# pvinvertershield32_v2.net
KiCad netlist of a schematic drawn in EAGLE
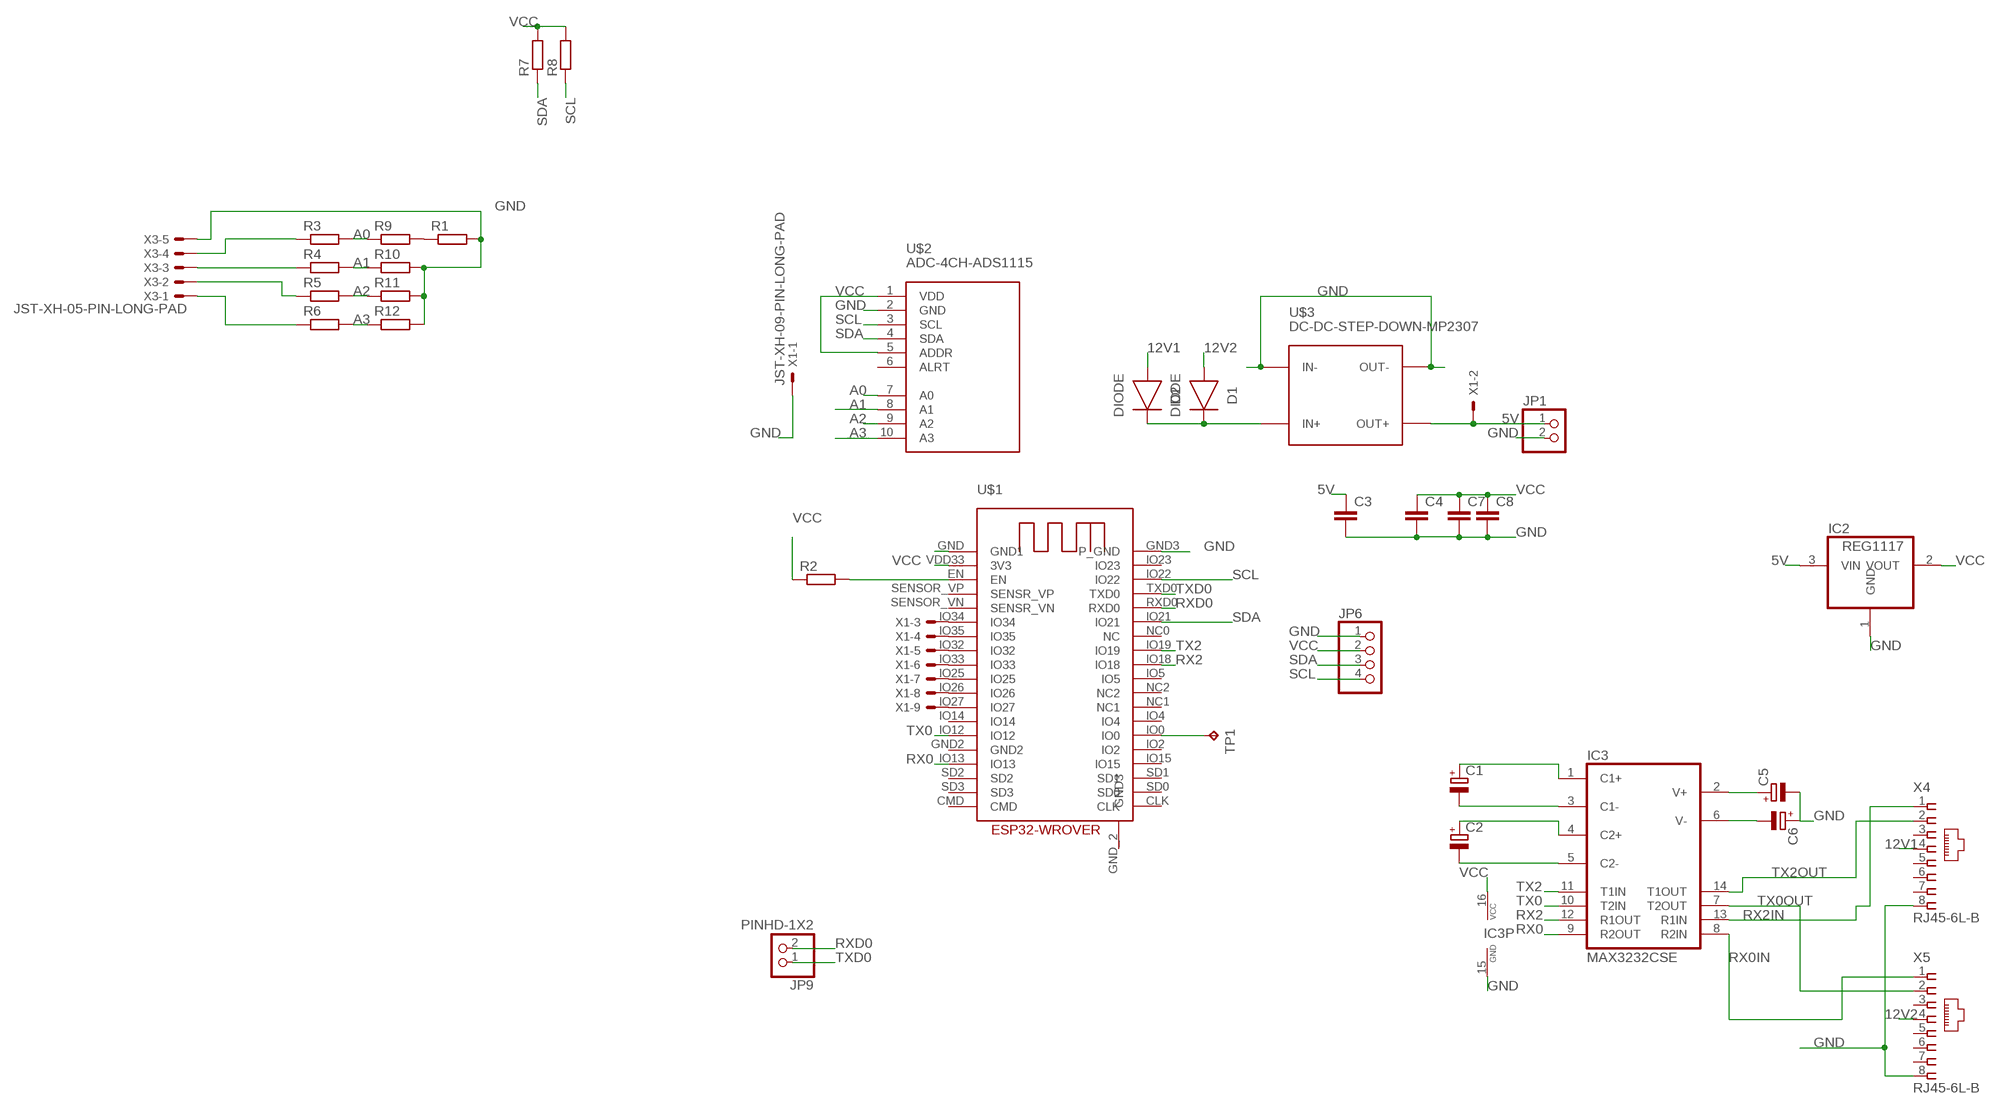
[diagram p0: schematic, sheet 1]

(export (version "E")
  (design (tool "Eeschema 10.0.6"))
  (components
    (comp (ref "C1")
      (value "CPOL-EUE2.5-6")
      (footprint "eagle-import:E2,5-6")
      (libsource (lib "eagle-import") (part "CPOL-EUE2.5-6"))
    )
    (comp (ref "C2")
      (value "CPOL-EUE2.5-6")
      (footprint "eagle-import:E2,5-6")
      (libsource (lib "eagle-import") (part "CPOL-EUE2.5-6"))
    )
    (comp (ref "C3")
      (value "C-EUC1210")
      (footprint "eagle-import:C1210")
      (libsource (lib "eagle-import") (part "C-EUC1210"))
    )
    (comp (ref "C4")
      (value "C-EUC1210")
      (footprint "eagle-import:C1210")
      (libsource (lib "eagle-import") (part "C-EUC1210"))
    )
    (comp (ref "C5")
      (value "CPOL-EUE2.5-6")
      (footprint "eagle-import:E2,5-6")
      (libsource (lib "eagle-import") (part "CPOL-EUE2.5-6"))
    )
    (comp (ref "C6")
      (value "CPOL-EUE2.5-6")
      (footprint "eagle-import:E2,5-6")
      (libsource (lib "eagle-import") (part "CPOL-EUE2.5-6"))
    )
    (comp (ref "C7")
      (value "C-EUC1210")
      (footprint "eagle-import:C1210")
      (libsource (lib "eagle-import") (part "C-EUC1210"))
    )
    (comp (ref "C8")
      (value "C-EUC1210")
      (footprint "eagle-import:C1210")
      (libsource (lib "eagle-import") (part "C-EUC1210"))
    )
    (comp (ref "D1")
      (value "DIODE")
      (footprint "eagle-import:DIOMELF5024")
      (libsource (lib "eagle-import") (part "DIODEDO-213AB(5025-METRIC)_"))
    )
    (comp (ref "D2")
      (value "DIODE")
      (footprint "eagle-import:DIOMELF5024")
      (libsource (lib "eagle-import") (part "DIODEDO-213AB(5025-METRIC)_"))
    )
    (comp (ref "IC2")
      (value "REG1117")
      (footprint "eagle-import:SOT223")
      (libsource (lib "eagle-import") (part "REG1117"))
    )
    (comp (ref "IC3")
      (value "MAX3232CSE")
      (footprint "eagle-import:SO16")
      (libsource (lib "eagle-import") (part "MAX3232SEC"))
    )
    (comp (ref "JP1")
      (value "PINHD-1X2")
      (footprint "eagle-import:1X02")
      (libsource (lib "eagle-import") (part "pinhead_325_PINHD-1X2"))
    )
    (comp (ref "JP6")
      (value "PINHD-1X4")
      (footprint "eagle-import:1X04")
      (libsource (lib "eagle-import") (part "PINHD-1X4"))
    )
    (comp (ref "JP9")
      (value "PINHD-1X2")
      (footprint "eagle-import:1X02")
      (libsource (lib "eagle-import") (part "PINHD-1X2"))
    )
    (comp (ref "R1")
      (value "R-EU_R0805")
      (footprint "eagle-import:R0805")
      (libsource (lib "eagle-import") (part "resistor_348_R-EU_R0805"))
    )
    (comp (ref "R2")
      (value "R-EU_R0805")
      (footprint "eagle-import:R0805")
      (libsource (lib "eagle-import") (part "R-EU_R0805"))
    )
    (comp (ref "R3")
      (value "R-EU_R0805")
      (footprint "eagle-import:R0805")
      (libsource (lib "eagle-import") (part "resistor_348_R-EU_R0805"))
    )
    (comp (ref "R4")
      (value "R-EU_R0805")
      (footprint "eagle-import:R0805")
      (libsource (lib "eagle-import") (part "resistor_348_R-EU_R0805"))
    )
    (comp (ref "R5")
      (value "R-EU_R0805")
      (footprint "eagle-import:R0805")
      (libsource (lib "eagle-import") (part "resistor_348_R-EU_R0805"))
    )
    (comp (ref "R6")
      (value "R-EU_R0805")
      (footprint "eagle-import:R0805")
      (libsource (lib "eagle-import") (part "resistor_348_R-EU_R0805"))
    )
    (comp (ref "R7")
      (value "R-EU_0207/10")
      (footprint "eagle-import:0207_10")
      (libsource (lib "eagle-import") (part "resistor_348_R-EU_0207/10"))
    )
    (comp (ref "R8")
      (value "R-EU_0207/10")
      (footprint "eagle-import:0207_10")
      (libsource (lib "eagle-import") (part "resistor_348_R-EU_0207/10"))
    )
    (comp (ref "R9")
      (value "R-EU_R0805")
      (footprint "eagle-import:R0805")
      (libsource (lib "eagle-import") (part "resistor_348_R-EU_R0805"))
    )
    (comp (ref "R10")
      (value "R-EU_R0805")
      (footprint "eagle-import:R0805")
      (libsource (lib "eagle-import") (part "resistor_348_R-EU_R0805"))
    )
    (comp (ref "R11")
      (value "R-EU_R0805")
      (footprint "eagle-import:R0805")
      (libsource (lib "eagle-import") (part "resistor_348_R-EU_R0805"))
    )
    (comp (ref "R12")
      (value "R-EU_R0805")
      (footprint "eagle-import:R0805")
      (libsource (lib "eagle-import") (part "resistor_348_R-EU_R0805"))
    )
    (comp (ref "TP1")
      (value "TPB2,54")
      (footprint "eagle-import:B2,54")
      (libsource (lib "eagle-import") (part "TPB2,54"))
    )
    (comp (ref "U$1")
      (value "ESP32-WROVER")
      (footprint "eagle-import:ESP32-WROVER")
      (libsource (lib "eagle-import") (part "ESP32-WROVER"))
    )
    (comp (ref "U$2")
      (value "ADC-4CH-ADS1115")
      (footprint "eagle-import:ADC-4CH-ADS1115")
      (libsource (lib "eagle-import") (part "ADC-4CH-ADS1115"))
    )
    (comp (ref "U$3")
      (value "DC-DC-STEP-DOWN-MP2307")
      (footprint "eagle-import:DC-DC-STEP-DOWN-MP2307")
      (libsource (lib "eagle-import") (part "DC-DC-STEP-DOWN-MP2307"))
    )
    (comp (ref "X1")
      (value "JST-XH-09-PIN-LONG-PAD")
      (footprint "eagle-import:JST-XH-09-PACKAGE-LONG-PAD")
      (libsource (lib "eagle-import") (part "JST-XH-09-PIN-LONG-PAD"))
    )
    (comp (ref "X3")
      (value "JST-XH-05-PIN-LONG-PAD")
      (footprint "eagle-import:JST-XH-05-PACKAGE-LONG-PAD")
      (libsource (lib "eagle-import") (part "JST-XH-05-PIN-LONG-PAD"))
    )
    (comp (ref "X4")
      (value "RJ45-6L-B")
      (footprint "eagle-import:RJ45-NO-SHIELD")
      (libsource (lib "eagle-import") (part "RJ45-6L-B"))
    )
    (comp (ref "X5")
      (value "RJ45-6L-B")
      (footprint "eagle-import:RJ45-NO-SHIELD")
      (libsource (lib "eagle-import") (part "RJ45-6L-B"))
    )
  )
  (nets
    (net (code "1") (name "/5V") (class "Default")
      (node (ref "C3") (pin "1") (pinfunction "1_1") (pintype "passive"))
      (node (ref "IC2") (pin "3") (pinfunction "VIN_3") (pintype "input"))
      (node (ref "JP1") (pin "1") (pinfunction "1_1") (pintype "passive"))
      (node (ref "U$3") (pin "OUT+") (pinfunction "OUT+_OUT+") (pintype "bidirectional"))
      (node (ref "X1") (pin "2") (pinfunction "S_2") (pintype "passive"))
    )
    (net (code "2") (name "/12V1") (class "Default")
      (node (ref "D2") (pin "2") (pinfunction "A_2") (pintype "passive"))
      (node (ref "X4") (pin "4") (pinfunction "4_4") (pintype "passive"))
    )
    (net (code "3") (name "/12V2") (class "Default")
      (node (ref "D1") (pin "2") (pinfunction "A_2") (pintype "passive"))
      (node (ref "X5") (pin "4") (pinfunction "4_4") (pintype "passive"))
    )
    (net (code "4") (name "/A0") (class "Default")
      (node (ref "R3") (pin "2") (pinfunction "2_2") (pintype "passive"))
      (node (ref "R9") (pin "1") (pinfunction "1_1") (pintype "passive"))
      (node (ref "U$2") (pin "7") (pinfunction "A0_7") (pintype "input"))
    )
    (net (code "5") (name "/A1") (class "Default")
      (node (ref "R10") (pin "1") (pinfunction "1_1") (pintype "passive"))
      (node (ref "R4") (pin "2") (pinfunction "2_2") (pintype "passive"))
      (node (ref "U$2") (pin "8") (pinfunction "A1_8") (pintype "input"))
    )
    (net (code "6") (name "/A2") (class "Default")
      (node (ref "R11") (pin "1") (pinfunction "1_1") (pintype "passive"))
      (node (ref "R5") (pin "2") (pinfunction "2_2") (pintype "passive"))
      (node (ref "U$2") (pin "9") (pinfunction "A2_9") (pintype "input"))
    )
    (net (code "7") (name "/A3") (class "Default")
      (node (ref "R12") (pin "1") (pinfunction "1_1") (pintype "passive"))
      (node (ref "R6") (pin "2") (pinfunction "2_2") (pintype "passive"))
      (node (ref "U$2") (pin "10") (pinfunction "A3_10") (pintype "input"))
    )
    (net (code "8") (name "/GND") (class "Default")
      (node (ref "C3") (pin "2") (pinfunction "2_2") (pintype "passive"))
      (node (ref "C4") (pin "2") (pinfunction "2_2") (pintype "passive"))
      (node (ref "C5") (pin "-") (pinfunction "-_-") (pintype "passive"))
      (node (ref "C6") (pin "+") (pinfunction "+_+") (pintype "passive"))
      (node (ref "C7") (pin "2") (pinfunction "2_2") (pintype "passive"))
      (node (ref "C8") (pin "2") (pinfunction "2_2") (pintype "passive"))
      (node (ref "IC2") (pin "1") (pinfunction "GND_1") (pintype "power_in"))
      (node (ref "IC3") (pin "15") (pinfunction "GND_15") (pintype "power_in"))
      (node (ref "JP1") (pin "2") (pinfunction "2_2") (pintype "passive"))
      (node (ref "JP6") (pin "1") (pinfunction "1_1") (pintype "passive"))
      (node (ref "R1") (pin "2") (pinfunction "2_2") (pintype "passive"))
      (node (ref "R10") (pin "2") (pinfunction "2_2") (pintype "passive"))
      (node (ref "R11") (pin "2") (pinfunction "2_2") (pintype "passive"))
      (node (ref "R12") (pin "2") (pinfunction "2_2") (pintype "passive"))
      (node (ref "U$1") (pin "GND") (pinfunction "GND1_GND") (pintype "bidirectional"))
      (node (ref "U$1") (pin "GND3") (pinfunction "P_GND_GND3") (pintype "bidirectional"))
      (node (ref "U$2") (pin "2") (pinfunction "GND_2") (pintype "power_in"))
      (node (ref "U$3") (pin "IN-") (pinfunction "IN-_IN-") (pintype "bidirectional"))
      (node (ref "U$3") (pin "OUT-") (pinfunction "OUT-_OUT-") (pintype "bidirectional"))
      (node (ref "X1") (pin "1") (pinfunction "S_1") (pintype "passive"))
      (node (ref "X3") (pin "5") (pinfunction "S_5") (pintype "passive"))
      (node (ref "X4") (pin "8") (pinfunction "8_8") (pintype "passive"))
      (node (ref "X5") (pin "8") (pinfunction "8_8") (pintype "passive"))
    )
    (net (code "9") (name "/RX0") (class "Default")
      (node (ref "IC3") (pin "9") (pinfunction "R2OUT_9") (pintype "output"))
      (node (ref "U$1") (pin "IO13") (pinfunction "IO13_IO13") (pintype "bidirectional"))
    )
    (net (code "10") (name "/RX0IN") (class "Default")
      (node (ref "IC3") (pin "8") (pinfunction "R2IN_8") (pintype "input"))
      (node (ref "X5") (pin "1") (pinfunction "1_1") (pintype "passive"))
    )
    (net (code "11") (name "/RX2") (class "Default")
      (node (ref "IC3") (pin "12") (pinfunction "R1OUT_12") (pintype "output"))
      (node (ref "U$1") (pin "IO18") (pinfunction "IO18_IO18") (pintype "bidirectional"))
    )
    (net (code "12") (name "/RX2IN") (class "Default")
      (node (ref "IC3") (pin "13") (pinfunction "R1IN_13") (pintype "input"))
      (node (ref "X4") (pin "1") (pinfunction "1_1") (pintype "passive"))
    )
    (net (code "13") (name "/RXD0") (class "Default")
      (node (ref "JP9") (pin "2") (pinfunction "2_2") (pintype "passive"))
      (node (ref "U$1") (pin "RXD0") (pinfunction "RXD0_RXD0") (pintype "bidirectional"))
    )
    (net (code "14") (name "/SCL") (class "Default")
      (node (ref "JP6") (pin "4") (pinfunction "4_4") (pintype "passive"))
      (node (ref "R8") (pin "1") (pinfunction "1_1") (pintype "passive"))
      (node (ref "U$1") (pin "IO22") (pinfunction "IO22_IO22") (pintype "bidirectional"))
      (node (ref "U$2") (pin "3") (pinfunction "SCL_3") (pintype "bidirectional"))
    )
    (net (code "15") (name "/SDA") (class "Default")
      (node (ref "JP6") (pin "3") (pinfunction "3_3") (pintype "passive"))
      (node (ref "R7") (pin "1") (pinfunction "1_1") (pintype "passive"))
      (node (ref "U$1") (pin "IO21") (pinfunction "IO21_IO21") (pintype "bidirectional"))
      (node (ref "U$2") (pin "4") (pinfunction "SDA_4") (pintype "bidirectional"))
    )
    (net (code "16") (name "/TX0") (class "Default")
      (node (ref "IC3") (pin "10") (pinfunction "T2IN_10") (pintype "input"))
      (node (ref "U$1") (pin "IO12") (pinfunction "IO12_IO12") (pintype "bidirectional"))
    )
    (net (code "17") (name "/TX0OUT") (class "Default")
      (node (ref "IC3") (pin "7") (pinfunction "T2OUT_7") (pintype "output"))
      (node (ref "X5") (pin "2") (pinfunction "2_2") (pintype "passive"))
    )
    (net (code "18") (name "/TX2") (class "Default")
      (node (ref "IC3") (pin "11") (pinfunction "T1IN_11") (pintype "input"))
      (node (ref "U$1") (pin "IO19") (pinfunction "IO19_IO19") (pintype "bidirectional"))
    )
    (net (code "19") (name "/TX2OUT") (class "Default")
      (node (ref "IC3") (pin "14") (pinfunction "T1OUT_14") (pintype "output"))
      (node (ref "X4") (pin "2") (pinfunction "2_2") (pintype "passive"))
    )
    (net (code "20") (name "/TXD0") (class "Default")
      (node (ref "JP9") (pin "1") (pinfunction "1_1") (pintype "passive"))
      (node (ref "U$1") (pin "TXD0") (pinfunction "TXD0_TXD0") (pintype "bidirectional"))
    )
    (net (code "21") (name "/VCC") (class "Default")
      (node (ref "C4") (pin "1") (pinfunction "1_1") (pintype "passive"))
      (node (ref "C7") (pin "1") (pinfunction "1_1") (pintype "passive"))
      (node (ref "C8") (pin "1") (pinfunction "1_1") (pintype "passive"))
      (node (ref "IC2") (pin "2") (pinfunction "VOUT_2") (pintype "output"))
      (node (ref "IC3") (pin "16") (pinfunction "VCC_16") (pintype "power_in"))
      (node (ref "JP6") (pin "2") (pinfunction "2_2") (pintype "passive"))
      (node (ref "R2") (pin "1") (pinfunction "1_1") (pintype "passive"))
      (node (ref "R7") (pin "2") (pinfunction "2_2") (pintype "passive"))
      (node (ref "R8") (pin "2") (pinfunction "2_2") (pintype "passive"))
      (node (ref "U$1") (pin "VDD33") (pinfunction "3V3_VDD33") (pintype "bidirectional"))
      (node (ref "U$2") (pin "1") (pinfunction "VDD_1") (pintype "power_in"))
      (node (ref "U$2") (pin "5") (pinfunction "ADDR_5") (pintype "bidirectional"))
    )
    (net (code "22") (name "Net-(D1-C)") (class "Default")
      (node (ref "D1") (pin "1") (pinfunction "C_1") (pintype "passive"))
      (node (ref "D2") (pin "1") (pinfunction "C_1") (pintype "passive"))
      (node (ref "U$3") (pin "IN+") (pinfunction "IN+_IN+") (pintype "bidirectional"))
    )
    (net (code "23") (name "Net-(IC3A-C1+)") (class "Default")
      (node (ref "C1") (pin "+") (pinfunction "+_+") (pintype "passive"))
      (node (ref "IC3") (pin "1") (pinfunction "C1+_1") (pintype "bidirectional"))
    )
    (net (code "24") (name "Net-(IC3A-C1-)") (class "Default")
      (node (ref "C1") (pin "-") (pinfunction "-_-") (pintype "passive"))
      (node (ref "IC3") (pin "3") (pinfunction "C1-_3") (pintype "bidirectional"))
    )
    (net (code "25") (name "Net-(IC3A-C2+)") (class "Default")
      (node (ref "C2") (pin "+") (pinfunction "+_+") (pintype "passive"))
      (node (ref "IC3") (pin "4") (pinfunction "C2+_4") (pintype "bidirectional"))
    )
    (net (code "26") (name "Net-(IC3A-C2-)") (class "Default")
      (node (ref "C2") (pin "-") (pinfunction "-_-") (pintype "passive"))
      (node (ref "IC3") (pin "5") (pinfunction "C2-_5") (pintype "bidirectional"))
    )
    (net (code "27") (name "Net-(IC3A-V+)") (class "Default")
      (node (ref "C5") (pin "+") (pinfunction "+_+") (pintype "passive"))
      (node (ref "IC3") (pin "2") (pinfunction "V+_2") (pintype "bidirectional"))
    )
    (net (code "28") (name "Net-(IC3A-V-)") (class "Default")
      (node (ref "C6") (pin "-") (pinfunction "-_-") (pintype "passive"))
      (node (ref "IC3") (pin "6") (pinfunction "V-_6") (pintype "bidirectional"))
    )
    (net (code "29") (name "Net-(R1-Pad1)") (class "Default")
      (node (ref "R1") (pin "1") (pinfunction "1_1") (pintype "passive"))
      (node (ref "R9") (pin "2") (pinfunction "2_2") (pintype "passive"))
    )
    (net (code "30") (name "Net-(R2-Pad2)") (class "Default")
      (node (ref "R2") (pin "2") (pinfunction "2_2") (pintype "passive"))
      (node (ref "U$1") (pin "EN") (pinfunction "EN_EN") (pintype "bidirectional"))
    )
    (net (code "31") (name "Net-(TP1-PadTP)") (class "Default")
      (node (ref "TP1") (pin "TP") (pinfunction "TP_TP") (pintype "input"))
      (node (ref "U$1") (pin "IO0") (pinfunction "IO0_IO0") (pintype "bidirectional"))
    )
    (net (code "32") (name "Net-(X1C-S)") (class "Default")
      (node (ref "U$1") (pin "IO34") (pinfunction "IO34_IO34") (pintype "bidirectional"))
      (node (ref "X1") (pin "3") (pinfunction "S_3") (pintype "passive"))
    )
    (net (code "33") (name "Net-(X1D-S)") (class "Default")
      (node (ref "U$1") (pin "IO35") (pinfunction "IO35_IO35") (pintype "bidirectional"))
      (node (ref "X1") (pin "4") (pinfunction "S_4") (pintype "passive"))
    )
    (net (code "34") (name "Net-(X1E-S)") (class "Default")
      (node (ref "U$1") (pin "IO32") (pinfunction "IO32_IO32") (pintype "bidirectional"))
      (node (ref "X1") (pin "5") (pinfunction "S_5") (pintype "passive"))
    )
    (net (code "35") (name "Net-(X1F-S)") (class "Default")
      (node (ref "U$1") (pin "IO33") (pinfunction "IO33_IO33") (pintype "bidirectional"))
      (node (ref "X1") (pin "6") (pinfunction "S_6") (pintype "passive"))
    )
    (net (code "36") (name "Net-(X1G-S)") (class "Default")
      (node (ref "U$1") (pin "IO25") (pinfunction "IO25_IO25") (pintype "bidirectional"))
      (node (ref "X1") (pin "7") (pinfunction "S_7") (pintype "passive"))
    )
    (net (code "37") (name "Net-(X1H-S)") (class "Default")
      (node (ref "U$1") (pin "IO26") (pinfunction "IO26_IO26") (pintype "bidirectional"))
      (node (ref "X1") (pin "8") (pinfunction "S_8") (pintype "passive"))
    )
    (net (code "38") (name "Net-(X1I-S)") (class "Default")
      (node (ref "U$1") (pin "IO27") (pinfunction "IO27_IO27") (pintype "bidirectional"))
      (node (ref "X1") (pin "9") (pinfunction "S_9") (pintype "passive"))
    )
    (net (code "39") (name "Net-(X3A-S)") (class "Default")
      (node (ref "R6") (pin "1") (pinfunction "1_1") (pintype "passive"))
      (node (ref "X3") (pin "1") (pinfunction "S_1") (pintype "passive"))
    )
    (net (code "40") (name "Net-(X3B-S)") (class "Default")
      (node (ref "R5") (pin "1") (pinfunction "1_1") (pintype "passive"))
      (node (ref "X3") (pin "2") (pinfunction "S_2") (pintype "passive"))
    )
    (net (code "41") (name "Net-(X3C-S)") (class "Default")
      (node (ref "R4") (pin "1") (pinfunction "1_1") (pintype "passive"))
      (node (ref "X3") (pin "3") (pinfunction "S_3") (pintype "passive"))
    )
    (net (code "42") (name "Net-(X3D-S)") (class "Default")
      (node (ref "R3") (pin "1") (pinfunction "1_1") (pintype "passive"))
      (node (ref "X3") (pin "4") (pinfunction "S_4") (pintype "passive"))
    )
    (net (code "43") (name "unconnected-(U$1-GND3-PadGND_2)") (class "Default")
      (node (ref "U$1") (pin "GND_2") (pinfunction "GND3_GND_2") (pintype "bidirectional"))
    )
    (net (code "44") (name "unconnected-(U$1-NC-PadNC0)") (class "Default")
      (node (ref "U$1") (pin "NC0") (pinfunction "NC_NC0") (pintype "bidirectional"))
    )
    (net (code "45") (name "unconnected-(U$1-PadCLK)") (class "Default")
      (node (ref "U$1") (pin "CLK") (pinfunction "CLK_CLK") (pintype "bidirectional"))
    )
    (net (code "46") (name "unconnected-(U$1-PadCMD)") (class "Default")
      (node (ref "U$1") (pin "CMD") (pinfunction "CMD_CMD") (pintype "bidirectional"))
    )
    (net (code "47") (name "unconnected-(U$1-PadGND2)") (class "Default")
      (node (ref "U$1") (pin "GND2") (pinfunction "GND2_GND2") (pintype "bidirectional"))
    )
    (net (code "48") (name "unconnected-(U$1-PadIO2)") (class "Default")
      (node (ref "U$1") (pin "IO2") (pinfunction "IO2_IO2") (pintype "bidirectional"))
    )
    (net (code "49") (name "unconnected-(U$1-PadIO4)") (class "Default")
      (node (ref "U$1") (pin "IO4") (pinfunction "IO4_IO4") (pintype "bidirectional"))
    )
    (net (code "50") (name "unconnected-(U$1-PadIO5)") (class "Default")
      (node (ref "U$1") (pin "IO5") (pinfunction "IO5_IO5") (pintype "bidirectional"))
    )
    (net (code "51") (name "unconnected-(U$1-PadIO14)") (class "Default")
      (node (ref "U$1") (pin "IO14") (pinfunction "IO14_IO14") (pintype "bidirectional"))
    )
    (net (code "52") (name "unconnected-(U$1-PadIO15)") (class "Default")
      (node (ref "U$1") (pin "IO15") (pinfunction "IO15_IO15") (pintype "bidirectional"))
    )
    (net (code "53") (name "unconnected-(U$1-PadIO23)") (class "Default")
      (node (ref "U$1") (pin "IO23") (pinfunction "IO23_IO23") (pintype "bidirectional"))
    )
    (net (code "54") (name "unconnected-(U$1-PadNC1)") (class "Default")
      (node (ref "U$1") (pin "NC1") (pinfunction "NC1_NC1") (pintype "bidirectional"))
    )
    (net (code "55") (name "unconnected-(U$1-PadNC2)") (class "Default")
      (node (ref "U$1") (pin "NC2") (pinfunction "NC2_NC2") (pintype "bidirectional"))
    )
    (net (code "56") (name "unconnected-(U$1-PadSD0)") (class "Default")
      (node (ref "U$1") (pin "SD0") (pinfunction "SD0_SD0") (pintype "bidirectional"))
    )
    (net (code "57") (name "unconnected-(U$1-PadSD1)") (class "Default")
      (node (ref "U$1") (pin "SD1") (pinfunction "SD1_SD1") (pintype "bidirectional"))
    )
    (net (code "58") (name "unconnected-(U$1-PadSD2)") (class "Default")
      (node (ref "U$1") (pin "SD2") (pinfunction "SD2_SD2") (pintype "bidirectional"))
    )
    (net (code "59") (name "unconnected-(U$1-PadSD3)") (class "Default")
      (node (ref "U$1") (pin "SD3") (pinfunction "SD3_SD3") (pintype "bidirectional"))
    )
    (net (code "60") (name "unconnected-(U$1-SENSR_VN-PadSENSOR_VN)") (class "Default")
      (node (ref "U$1") (pin "SENSOR_VN") (pinfunction "SENSR_VN_SENSOR_VN") (pintype "bidirectional"))
    )
    (net (code "61") (name "unconnected-(U$1-SENSR_VP-PadSENSOR_VP)") (class "Default")
      (node (ref "U$1") (pin "SENSOR_VP") (pinfunction "SENSR_VP_SENSOR_VP") (pintype "bidirectional"))
    )
    (net (code "62") (name "unconnected-(U$2-ALRT-Pad6)") (class "Default")
      (node (ref "U$2") (pin "6") (pinfunction "ALRT_6") (pintype "bidirectional"))
    )
    (net (code "63") (name "unconnected-(X4-Pad3)") (class "Default")
      (node (ref "X4") (pin "3") (pinfunction "3_3") (pintype "passive"))
    )
    (net (code "64") (name "unconnected-(X4-Pad5)") (class "Default")
      (node (ref "X4") (pin "5") (pinfunction "5_5") (pintype "passive"))
    )
    (net (code "65") (name "unconnected-(X4-Pad6)") (class "Default")
      (node (ref "X4") (pin "6") (pinfunction "6_6") (pintype "passive"))
    )
    (net (code "66") (name "unconnected-(X4-Pad7)") (class "Default")
      (node (ref "X4") (pin "7") (pinfunction "7_7") (pintype "passive"))
    )
    (net (code "67") (name "unconnected-(X5-Pad3)") (class "Default")
      (node (ref "X5") (pin "3") (pinfunction "3_3") (pintype "passive"))
    )
    (net (code "68") (name "unconnected-(X5-Pad5)") (class "Default")
      (node (ref "X5") (pin "5") (pinfunction "5_5") (pintype "passive"))
    )
    (net (code "69") (name "unconnected-(X5-Pad6)") (class "Default")
      (node (ref "X5") (pin "6") (pinfunction "6_6") (pintype "passive"))
    )
    (net (code "70") (name "unconnected-(X5-Pad7)") (class "Default")
      (node (ref "X5") (pin "7") (pinfunction "7_7") (pintype "passive"))
    )
  )
)
